# IoT_2015-1.net
KiCad netlist of a schematic drawn in EAGLE
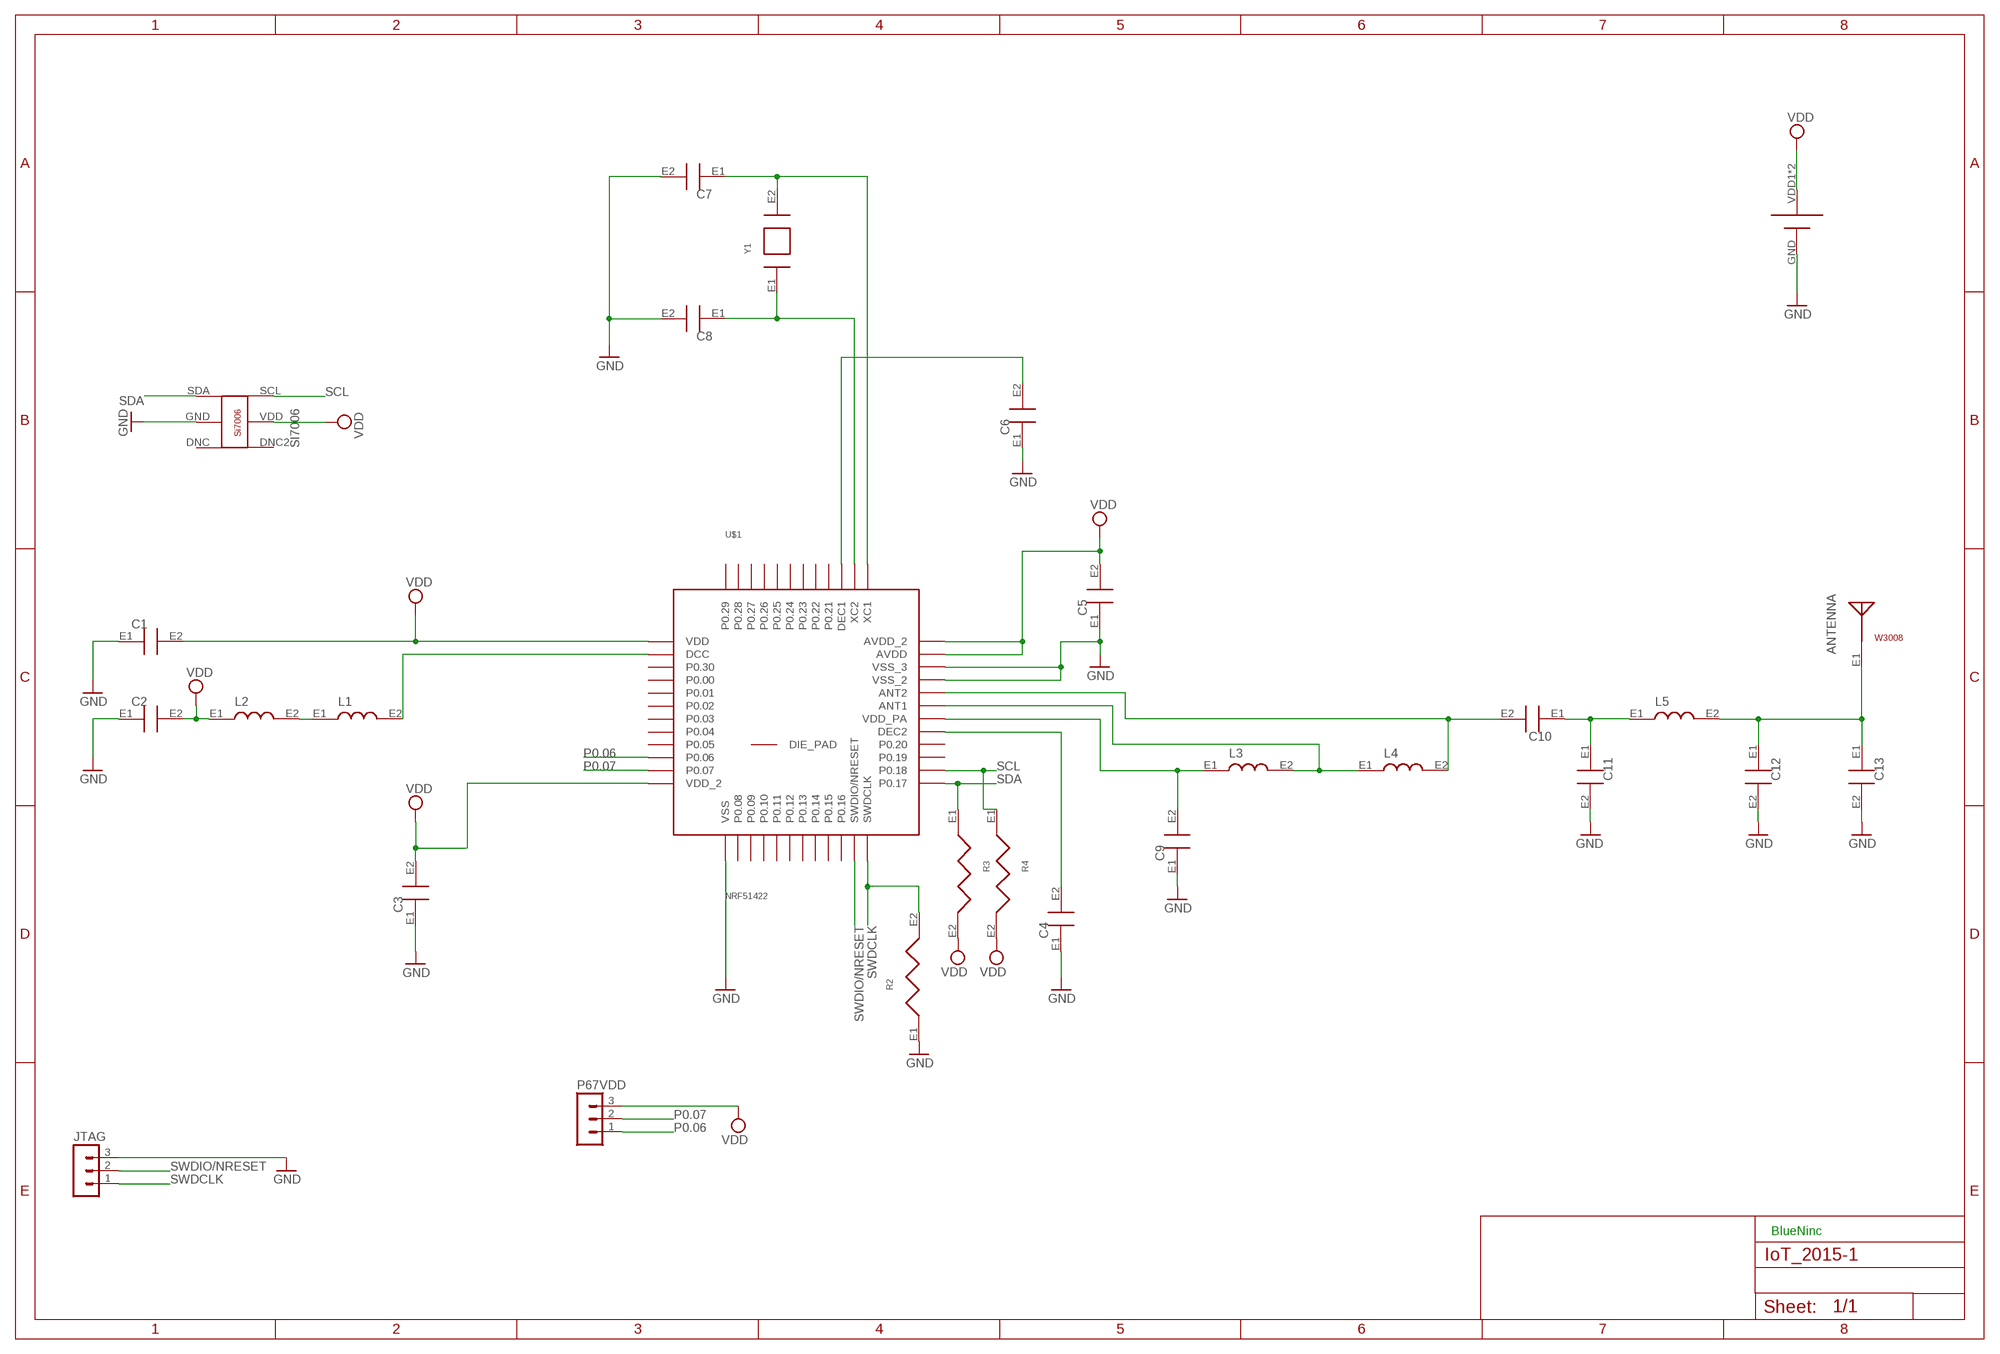
[diagram p0: schematic, sheet 1]

(export (version "E")
  (design (tool "Eeschema 10.0.6"))
  (components
    (comp (ref "ANTENNA")
      (value "W3008")
      (footprint "eagle-import:W3008")
      (libsource (lib "eagle-import") (part "W3008"))
    )
    (comp (ref "BATTERY")
      (value "BAT-HLD-001")
      (footprint "eagle-import:BAT-HLD-001")
      (libsource (lib "eagle-import") (part "BAT-HLD-001"))
    )
    (comp (ref "C1")
      (value "VJ1603_W1BC")
      (footprint "eagle-import:VJ1603_W1BC")
      (libsource (lib "eagle-import") (part "VJ1603_W1BC"))
    )
    (comp (ref "C2")
      (value "VJ1603_W1BC")
      (footprint "eagle-import:VJ1603_W1BC")
      (libsource (lib "eagle-import") (part "VJ1603_W1BC"))
    )
    (comp (ref "C3")
      (value "VJ1603_W1BC")
      (footprint "eagle-import:VJ1603_W1BC")
      (libsource (lib "eagle-import") (part "VJ1603_W1BC"))
    )
    (comp (ref "C4")
      (value "VJ1603_W1BC")
      (footprint "eagle-import:VJ1603_W1BC")
      (libsource (lib "eagle-import") (part "VJ1603_W1BC"))
    )
    (comp (ref "C5")
      (value "VJ1603_W1BC")
      (footprint "eagle-import:VJ1603_W1BC")
      (libsource (lib "eagle-import") (part "VJ1603_W1BC"))
    )
    (comp (ref "C6")
      (value "VJ1603_W1BC")
      (footprint "eagle-import:VJ1603_W1BC")
      (libsource (lib "eagle-import") (part "VJ1603_W1BC"))
    )
    (comp (ref "C7")
      (value "VJ1603_W1BC")
      (footprint "eagle-import:VJ1603_W1BC")
      (libsource (lib "eagle-import") (part "VJ1603_W1BC"))
    )
    (comp (ref "C8")
      (value "VJ1603_W1BC")
      (footprint "eagle-import:VJ1603_W1BC")
      (libsource (lib "eagle-import") (part "VJ1603_W1BC"))
    )
    (comp (ref "C9")
      (value "VJ1603_W1BC")
      (footprint "eagle-import:VJ1603_W1BC")
      (libsource (lib "eagle-import") (part "VJ1603_W1BC"))
    )
    (comp (ref "C10")
      (value "VJ1603_W1BC")
      (footprint "eagle-import:VJ1603_W1BC")
      (libsource (lib "eagle-import") (part "VJ1603_W1BC"))
    )
    (comp (ref "C11")
      (value "VJ1603_W1BC")
      (footprint "eagle-import:VJ1603_W1BC")
      (libsource (lib "eagle-import") (part "VJ1603_W1BC"))
    )
    (comp (ref "C12")
      (value "VJ1603_W1BC")
      (footprint "eagle-import:VJ1603_W1BC")
      (libsource (lib "eagle-import") (part "VJ1603_W1BC"))
    )
    (comp (ref "C13")
      (value "VJ1603_W1BC")
      (footprint "eagle-import:VJ1603_W1BC")
      (libsource (lib "eagle-import") (part "VJ1603_W1BC"))
    )
    (comp (ref "JTAG")
      (value "MA03-1")
      (footprint "eagle-import:MA03-1")
      (libsource (lib "eagle-import") (part "MA03-1"))
    )
    (comp (ref "L1")
      (value "JTI_CAT_2012_INDUCTORS_CHIP-242427")
      (footprint "eagle-import:JTI_CAT_2012_INDUCTORS_CHIP-242427")
      (libsource (lib "eagle-import") (part "JTI_CAT_2012_INDUCTORS_CHIP-242427"))
    )
    (comp (ref "L2")
      (value "JTI_CAT_2012_INDUCTORS_CHIP-242427")
      (footprint "eagle-import:JTI_CAT_2012_INDUCTORS_CHIP-242427")
      (libsource (lib "eagle-import") (part "JTI_CAT_2012_INDUCTORS_CHIP-242427"))
    )
    (comp (ref "L3")
      (value "JTI_CAT_2012_INDUCTORS_CHIP-242427")
      (footprint "eagle-import:JTI_CAT_2012_INDUCTORS_CHIP-242427")
      (libsource (lib "eagle-import") (part "JTI_CAT_2012_INDUCTORS_CHIP-242427"))
    )
    (comp (ref "L4")
      (value "JTI_CAT_2012_INDUCTORS_CHIP-242427")
      (footprint "eagle-import:JTI_CAT_2012_INDUCTORS_CHIP-242427")
      (libsource (lib "eagle-import") (part "JTI_CAT_2012_INDUCTORS_CHIP-242427"))
    )
    (comp (ref "L5")
      (value "JTI_CAT_2012_INDUCTORS_CHIP-242427")
      (footprint "eagle-import:JTI_CAT_2012_INDUCTORS_CHIP-242427")
      (libsource (lib "eagle-import") (part "JTI_CAT_2012_INDUCTORS_CHIP-242427"))
    )
    (comp (ref "P67VDD")
      (value "MA03-1")
      (footprint "eagle-import:MA03-1")
      (libsource (lib "eagle-import") (part "MA03-1"))
    )
    (comp (ref "R2")
      (value "ERJ-3GEYJ103V")
      (footprint "eagle-import:ERJ-3GEYJ103V")
      (libsource (lib "eagle-import") (part "ERJ-3GEYJ103V"))
    )
    (comp (ref "R3")
      (value "ERJ-3GEYJ103V")
      (footprint "eagle-import:ERJ-3GEYJ103V")
      (libsource (lib "eagle-import") (part "ERJ-3GEYJ103V"))
    )
    (comp (ref "R4")
      (value "ERJ-3GEYJ103V")
      (footprint "eagle-import:ERJ-3GEYJ103V")
      (libsource (lib "eagle-import") (part "ERJ-3GEYJ103V"))
    )
    (comp (ref "SI7006")
      (value "SI7006-A20-IM")
      (footprint "eagle-import:SI7006-A20-IM")
      (libsource (lib "eagle-import") (part "SI7006-A20-IM"))
    )
    (comp (ref "U$1")
      (value "NRF51422")
      (footprint "eagle-import:QFN48")
      (libsource (lib "eagle-import") (part "NRF51422"))
    )
    (comp (ref "Y1")
      (value "ABLS-16.000MHZ-B4-T")
      (footprint "eagle-import:ABLS-16.000MHZ-B4-T")
      (libsource (lib "eagle-import") (part "ABLS-16.000MHZ-B4-T"))
    )
  )
  (nets
    (net (code "1") (name "/P0.06") (class "Default")
      (node (ref "P67VDD") (pin "1") (pinfunction "1_1") (pintype "passive"))
      (node (ref "U$1") (pin "10") (pinfunction "P0.06_10") (pintype "bidirectional"))
    )
    (net (code "2") (name "/P0.07") (class "Default")
      (node (ref "P67VDD") (pin "2") (pinfunction "2_2") (pintype "passive"))
      (node (ref "U$1") (pin "11") (pinfunction "P0.07_11") (pintype "bidirectional"))
    )
    (net (code "3") (name "/SCL") (class "Default")
      (node (ref "R4") (pin "E1") (pinfunction "E1_E1") (pintype "bidirectional"))
      (node (ref "SI7006") (pin "SCL") (pinfunction "SCL_SCL") (pintype "bidirectional"))
      (node (ref "U$1") (pin "26") (pinfunction "P0.18_26") (pintype "bidirectional"))
    )
    (net (code "4") (name "/SDA") (class "Default")
      (node (ref "R3") (pin "E1") (pinfunction "E1_E1") (pintype "bidirectional"))
      (node (ref "SI7006") (pin "SDA") (pinfunction "SDA_SDA") (pintype "bidirectional"))
      (node (ref "U$1") (pin "25") (pinfunction "P0.17_25") (pintype "bidirectional"))
    )
    (net (code "5") (name "/SWDCLK") (class "Default")
      (node (ref "JTAG") (pin "1") (pinfunction "1_1") (pintype "passive"))
      (node (ref "R2") (pin "E2") (pinfunction "E2_E2") (pintype "bidirectional"))
      (node (ref "U$1") (pin "24") (pinfunction "SWDCLK_24") (pintype "bidirectional"))
    )
    (net (code "6") (name "/SWDIO{slash}NRESET") (class "Default")
      (node (ref "JTAG") (pin "2") (pinfunction "2_2") (pintype "passive"))
      (node (ref "U$1") (pin "23") (pinfunction "SWDIO/NRESET_23") (pintype "bidirectional"))
    )
    (net (code "7") (name "GND") (class "Default")
      (node (ref "BATTERY") (pin "GND") (pinfunction "GND_GND") (pintype "bidirectional"))
      (node (ref "C1") (pin "E1") (pinfunction "E1_E1") (pintype "bidirectional"))
      (node (ref "C11") (pin "E2") (pinfunction "E2_E2") (pintype "bidirectional"))
      (node (ref "C12") (pin "E2") (pinfunction "E2_E2") (pintype "bidirectional"))
      (node (ref "C13") (pin "E2") (pinfunction "E2_E2") (pintype "bidirectional"))
      (node (ref "C2") (pin "E1") (pinfunction "E1_E1") (pintype "bidirectional"))
      (node (ref "C3") (pin "E1") (pinfunction "E1_E1") (pintype "bidirectional"))
      (node (ref "C4") (pin "E1") (pinfunction "E1_E1") (pintype "bidirectional"))
      (node (ref "C5") (pin "E1") (pinfunction "E1_E1") (pintype "bidirectional"))
      (node (ref "C6") (pin "E1") (pinfunction "E1_E1") (pintype "bidirectional"))
      (node (ref "C7") (pin "E2") (pinfunction "E2_E2") (pintype "bidirectional"))
      (node (ref "C8") (pin "E2") (pinfunction "E2_E2") (pintype "bidirectional"))
      (node (ref "C9") (pin "E1") (pinfunction "E1_E1") (pintype "bidirectional"))
      (node (ref "JTAG") (pin "3") (pinfunction "3_3") (pintype "passive"))
      (node (ref "R2") (pin "E1") (pinfunction "E1_E1") (pintype "bidirectional"))
      (node (ref "SI7006") (pin "GND") (pinfunction "GND_GND") (pintype "bidirectional"))
      (node (ref "U$1") (pin "13") (pinfunction "VSS_13") (pintype "bidirectional"))
      (node (ref "U$1") (pin "33") (pinfunction "VSS_2_33") (pintype "bidirectional"))
      (node (ref "U$1") (pin "34") (pinfunction "VSS_3_34") (pintype "bidirectional"))
    )
    (net (code "8") (name "Net-(ANTENNA-PadE1)") (class "Default")
      (node (ref "ANTENNA") (pin "E1") (pinfunction "E1_E1") (pintype "bidirectional"))
      (node (ref "C12") (pin "E1") (pinfunction "E1_E1") (pintype "bidirectional"))
      (node (ref "C13") (pin "E1") (pinfunction "E1_E1") (pintype "bidirectional"))
      (node (ref "L5") (pin "E2") (pinfunction "E2_E2") (pintype "bidirectional"))
    )
    (net (code "9") (name "Net-(C10-PadE1)") (class "Default")
      (node (ref "C10") (pin "E1") (pinfunction "E1_E1") (pintype "bidirectional"))
      (node (ref "C11") (pin "E1") (pinfunction "E1_E1") (pintype "bidirectional"))
      (node (ref "L5") (pin "E1") (pinfunction "E1_E1") (pintype "bidirectional"))
    )
    (net (code "10") (name "Net-(L1-PadE1)") (class "Default")
      (node (ref "L1") (pin "E1") (pinfunction "E1_E1") (pintype "bidirectional"))
      (node (ref "L2") (pin "E2") (pinfunction "E2_E2") (pintype "bidirectional"))
    )
    (net (code "11") (name "Net-(U$1-ANT1)") (class "Default")
      (node (ref "L3") (pin "E2") (pinfunction "E2_E2") (pintype "bidirectional"))
      (node (ref "L4") (pin "E1") (pinfunction "E1_E1") (pintype "bidirectional"))
      (node (ref "U$1") (pin "31") (pinfunction "ANT1_31") (pintype "bidirectional"))
    )
    (net (code "12") (name "Net-(U$1-ANT2)") (class "Default")
      (node (ref "C10") (pin "E2") (pinfunction "E2_E2") (pintype "bidirectional"))
      (node (ref "L4") (pin "E2") (pinfunction "E2_E2") (pintype "bidirectional"))
      (node (ref "U$1") (pin "32") (pinfunction "ANT2_32") (pintype "bidirectional"))
    )
    (net (code "13") (name "Net-(U$1-DCC)") (class "Default")
      (node (ref "L1") (pin "E2") (pinfunction "E2_E2") (pintype "bidirectional"))
      (node (ref "U$1") (pin "2") (pinfunction "DCC_2") (pintype "bidirectional"))
    )
    (net (code "14") (name "Net-(U$1-DEC1)") (class "Default")
      (node (ref "C6") (pin "E2") (pinfunction "E2_E2") (pintype "bidirectional"))
      (node (ref "U$1") (pin "39") (pinfunction "DEC1_39") (pintype "bidirectional"))
    )
    (net (code "15") (name "Net-(U$1-DEC2)") (class "Default")
      (node (ref "C4") (pin "E2") (pinfunction "E2_E2") (pintype "bidirectional"))
      (node (ref "U$1") (pin "29") (pinfunction "DEC2_29") (pintype "bidirectional"))
    )
    (net (code "16") (name "Net-(U$1-VDD_PA)") (class "Default")
      (node (ref "C9") (pin "E2") (pinfunction "E2_E2") (pintype "bidirectional"))
      (node (ref "L3") (pin "E1") (pinfunction "E1_E1") (pintype "bidirectional"))
      (node (ref "U$1") (pin "30") (pinfunction "VDD_PA_30") (pintype "bidirectional"))
    )
    (net (code "17") (name "Net-(U$1-XC1)") (class "Default")
      (node (ref "C7") (pin "E1") (pinfunction "E1_E1") (pintype "bidirectional"))
      (node (ref "U$1") (pin "37") (pinfunction "XC1_37") (pintype "bidirectional"))
      (node (ref "Y1") (pin "E2") (pinfunction "E2_E2") (pintype "bidirectional"))
    )
    (net (code "18") (name "Net-(U$1-XC2)") (class "Default")
      (node (ref "C8") (pin "E1") (pinfunction "E1_E1") (pintype "bidirectional"))
      (node (ref "U$1") (pin "38") (pinfunction "XC2_38") (pintype "bidirectional"))
      (node (ref "Y1") (pin "E1") (pinfunction "E1_E1") (pintype "bidirectional"))
    )
    (net (code "19") (name "VDD") (class "Default")
      (node (ref "BATTERY") (pin "VDD1") (pinfunction "VDD_VDD1") (pintype "bidirectional"))
      (node (ref "BATTERY") (pin "VDD2") (pinfunction "VDD_VDD2") (pintype "bidirectional"))
      (node (ref "C1") (pin "E2") (pinfunction "E2_E2") (pintype "bidirectional"))
      (node (ref "C2") (pin "E2") (pinfunction "E2_E2") (pintype "bidirectional"))
      (node (ref "C3") (pin "E2") (pinfunction "E2_E2") (pintype "bidirectional"))
      (node (ref "C5") (pin "E2") (pinfunction "E2_E2") (pintype "bidirectional"))
      (node (ref "L2") (pin "E1") (pinfunction "E1_E1") (pintype "bidirectional"))
      (node (ref "P67VDD") (pin "3") (pinfunction "3_3") (pintype "passive"))
      (node (ref "R3") (pin "E2") (pinfunction "E2_E2") (pintype "bidirectional"))
      (node (ref "R4") (pin "E2") (pinfunction "E2_E2") (pintype "bidirectional"))
      (node (ref "SI7006") (pin "VDD") (pinfunction "VDD_VDD") (pintype "bidirectional"))
      (node (ref "U$1") (pin "1") (pinfunction "VDD_1") (pintype "bidirectional"))
      (node (ref "U$1") (pin "12") (pinfunction "VDD_2_12") (pintype "bidirectional"))
      (node (ref "U$1") (pin "35") (pinfunction "AVDD_35") (pintype "bidirectional"))
      (node (ref "U$1") (pin "36") (pinfunction "AVDD_2_36") (pintype "bidirectional"))
    )
    (net (code "20") (name "unconnected-(SI7006-PadDNC)") (class "Default")
      (node (ref "SI7006") (pin "DNC") (pinfunction "DNC_DNC") (pintype "bidirectional"))
    )
    (net (code "21") (name "unconnected-(SI7006-PadDNC2)") (class "Default")
      (node (ref "SI7006") (pin "DNC2") (pinfunction "DNC2_DNC2") (pintype "bidirectional"))
    )
    (net (code "22") (name "unconnected-(U$1-DIE_PAD-PadGND)") (class "Default")
      (node (ref "U$1") (pin "GND") (pinfunction "DIE_PAD_GND") (pintype "bidirectional"))
    )
    (net (code "23") (name "unconnected-(U$1-P0.00-Pad4)") (class "Default")
      (node (ref "U$1") (pin "4") (pinfunction "P0.00_4") (pintype "bidirectional"))
    )
    (net (code "24") (name "unconnected-(U$1-P0.01-Pad5)") (class "Default")
      (node (ref "U$1") (pin "5") (pinfunction "P0.01_5") (pintype "bidirectional"))
    )
    (net (code "25") (name "unconnected-(U$1-P0.02-Pad6)") (class "Default")
      (node (ref "U$1") (pin "6") (pinfunction "P0.02_6") (pintype "bidirectional"))
    )
    (net (code "26") (name "unconnected-(U$1-P0.03-Pad7)") (class "Default")
      (node (ref "U$1") (pin "7") (pinfunction "P0.03_7") (pintype "bidirectional"))
    )
    (net (code "27") (name "unconnected-(U$1-P0.04-Pad8)") (class "Default")
      (node (ref "U$1") (pin "8") (pinfunction "P0.04_8") (pintype "bidirectional"))
    )
    (net (code "28") (name "unconnected-(U$1-P0.05-Pad9)") (class "Default")
      (node (ref "U$1") (pin "9") (pinfunction "P0.05_9") (pintype "bidirectional"))
    )
    (net (code "29") (name "unconnected-(U$1-P0.08-Pad14)") (class "Default")
      (node (ref "U$1") (pin "14") (pinfunction "P0.08_14") (pintype "bidirectional"))
    )
    (net (code "30") (name "unconnected-(U$1-P0.09-Pad15)") (class "Default")
      (node (ref "U$1") (pin "15") (pinfunction "P0.09_15") (pintype "bidirectional"))
    )
    (net (code "31") (name "unconnected-(U$1-P0.10-Pad16)") (class "Default")
      (node (ref "U$1") (pin "16") (pinfunction "P0.10_16") (pintype "bidirectional"))
    )
    (net (code "32") (name "unconnected-(U$1-P0.11-Pad17)") (class "Default")
      (node (ref "U$1") (pin "17") (pinfunction "P0.11_17") (pintype "bidirectional"))
    )
    (net (code "33") (name "unconnected-(U$1-P0.12-Pad18)") (class "Default")
      (node (ref "U$1") (pin "18") (pinfunction "P0.12_18") (pintype "bidirectional"))
    )
    (net (code "34") (name "unconnected-(U$1-P0.13-Pad19)") (class "Default")
      (node (ref "U$1") (pin "19") (pinfunction "P0.13_19") (pintype "bidirectional"))
    )
    (net (code "35") (name "unconnected-(U$1-P0.14-Pad20)") (class "Default")
      (node (ref "U$1") (pin "20") (pinfunction "P0.14_20") (pintype "bidirectional"))
    )
    (net (code "36") (name "unconnected-(U$1-P0.15-Pad21)") (class "Default")
      (node (ref "U$1") (pin "21") (pinfunction "P0.15_21") (pintype "bidirectional"))
    )
    (net (code "37") (name "unconnected-(U$1-P0.16-Pad22)") (class "Default")
      (node (ref "U$1") (pin "22") (pinfunction "P0.16_22") (pintype "bidirectional"))
    )
    (net (code "38") (name "unconnected-(U$1-P0.19-Pad27)") (class "Default")
      (node (ref "U$1") (pin "27") (pinfunction "P0.19_27") (pintype "bidirectional"))
    )
    (net (code "39") (name "unconnected-(U$1-P0.20-Pad28)") (class "Default")
      (node (ref "U$1") (pin "28") (pinfunction "P0.20_28") (pintype "bidirectional"))
    )
    (net (code "40") (name "unconnected-(U$1-P0.21-Pad40)") (class "Default")
      (node (ref "U$1") (pin "40") (pinfunction "P0.21_40") (pintype "bidirectional"))
    )
    (net (code "41") (name "unconnected-(U$1-P0.22-Pad41)") (class "Default")
      (node (ref "U$1") (pin "41") (pinfunction "P0.22_41") (pintype "bidirectional"))
    )
    (net (code "42") (name "unconnected-(U$1-P0.23-Pad42)") (class "Default")
      (node (ref "U$1") (pin "42") (pinfunction "P0.23_42") (pintype "bidirectional"))
    )
    (net (code "43") (name "unconnected-(U$1-P0.24-Pad43)") (class "Default")
      (node (ref "U$1") (pin "43") (pinfunction "P0.24_43") (pintype "bidirectional"))
    )
    (net (code "44") (name "unconnected-(U$1-P0.25-Pad44)") (class "Default")
      (node (ref "U$1") (pin "44") (pinfunction "P0.25_44") (pintype "bidirectional"))
    )
    (net (code "45") (name "unconnected-(U$1-P0.26-Pad45)") (class "Default")
      (node (ref "U$1") (pin "45") (pinfunction "P0.26_45") (pintype "bidirectional"))
    )
    (net (code "46") (name "unconnected-(U$1-P0.27-Pad46)") (class "Default")
      (node (ref "U$1") (pin "46") (pinfunction "P0.27_46") (pintype "bidirectional"))
    )
    (net (code "47") (name "unconnected-(U$1-P0.28-Pad47)") (class "Default")
      (node (ref "U$1") (pin "47") (pinfunction "P0.28_47") (pintype "bidirectional"))
    )
    (net (code "48") (name "unconnected-(U$1-P0.29-Pad48)") (class "Default")
      (node (ref "U$1") (pin "48") (pinfunction "P0.29_48") (pintype "bidirectional"))
    )
    (net (code "49") (name "unconnected-(U$1-P0.30-Pad3)") (class "Default")
      (node (ref "U$1") (pin "3") (pinfunction "P0.30_3") (pintype "bidirectional"))
    )
  )
)
